# Magileff_transporter.net
KiCad netlist of a schematic drawn in EAGLE
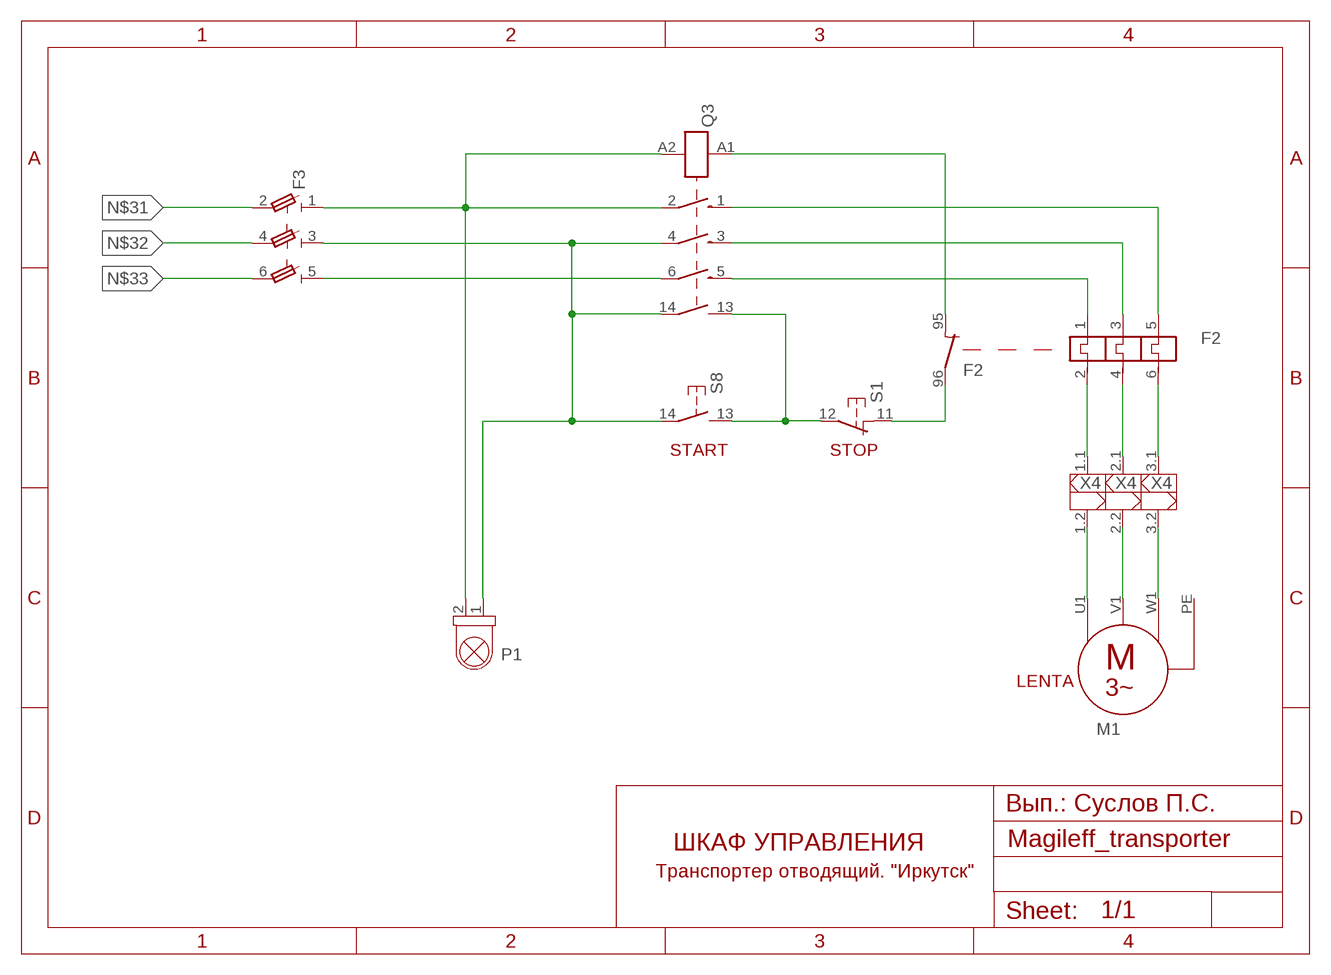
[diagram p0: schematic, sheet 1]

(export (version "E")
  (design (tool "Eeschema 10.0.6"))
  (components
    (comp (ref "F2")
      (value "MOTORSCHUTZSCHALTER_3-POL_THERM_AUSLOESUNG_HILFSKONTAKTE")
      (footprint "eagle-import:MOTORSCHUTZSCHALTER_3-POL_THERM_AUSLOESUNG_HILFSKONTAKT_95_96_97_98")
      (libsource (lib "eagle-import") (part "MOTORSCHUTZSCHALTER_3-POL_THERM_AUSLOESUNG_HILFSKONTAKTE"))
    )
    (comp (ref "F3")
      (value "TRENNSICHERUNG_3-POL")
      (footprint "eagle-import:TRENNSICHERUNG_3-POL")
      (libsource (lib "eagle-import") (part "TRENNSICHERUNG_3-POL"))
    )
    (comp (ref "M1")
      (value "MOTOR_3-POL_PE")
      (footprint "eagle-import:MOTOR_3-POL_PE")
      (libsource (lib "eagle-import") (part "MOTOR_3-POL_PE"))
    )
    (comp (ref "P1")
      (value "BLINK/BLITZLEUCHTE")
      (footprint "eagle-import:LAMPE")
      (libsource (lib "eagle-import") (part "BLINK/BLITZLEUCHTE"))
    )
    (comp (ref "Q3")
      (value "HAUPTSCHUETZ_3-POL_HILFSKONTAKT_13-14_OHNE_KONTAKTSPIEGEL")
      (footprint "eagle-import:HAUPTSCHUETZ_3-POL+HILFSKONTAKT_13-14_OHNE_KONTAKTSPIEGEL")
      (libsource (lib "eagle-import") (part "HAUPTSCHUETZ_3-POL_HILFSKONTAKT_13-14_OHNE_KONTAKTSPIEGEL"))
    )
    (comp (ref "S1")
      (value "OEFFNER_TASTSCHALTER")
      (footprint "eagle-import:OEFFNER_TASTSCHALTER")
      (libsource (lib "eagle-import") (part "OEFFNER_TASTSCHALTER"))
    )
    (comp (ref "S8")
      (value "SCHLIESSER_TASTSCHALTER")
      (footprint "eagle-import:SCHLIESSER_TASTSCHALTER")
      (libsource (lib "eagle-import") (part "SCHLIESSER_TASTSCHALTER"))
    )
    (comp (ref "X4")
      (value "KLEMME-2_3-BRUECKE")
      (footprint "eagle-import:KLEMME-2_3-BRUECKE")
      (libsource (lib "eagle-import") (part "KLEMME-2_3-BRUECKE"))
    )
  )
  (nets
    (net (code "1") (name "N$31") (class "Default")
      (node (ref "F3") (pin "2") (pinfunction "2_2") (pintype "passive"))
    )
    (net (code "2") (name "N$32") (class "Default")
      (node (ref "F3") (pin "4") (pinfunction "4_4") (pintype "passive"))
    )
    (net (code "3") (name "N$33") (class "Default")
      (node (ref "F3") (pin "6") (pinfunction "6_6") (pintype "passive"))
    )
    (net (code "4") (name "Net-(F2-Pad1)") (class "Default")
      (node (ref "F2") (pin "1") (pinfunction "1_1") (pintype "passive"))
      (node (ref "Q3") (pin "5") (pinfunction "5_5") (pintype "passive"))
    )
    (net (code "5") (name "Net-(F2-Pad3)") (class "Default")
      (node (ref "F2") (pin "3") (pinfunction "3_3") (pintype "passive"))
      (node (ref "Q3") (pin "3") (pinfunction "3_3") (pintype "passive"))
    )
    (net (code "6") (name "Net-(F2-Pad5)") (class "Default")
      (node (ref "F2") (pin "5") (pinfunction "5_5") (pintype "passive"))
      (node (ref "Q3") (pin "1") (pinfunction "1_1") (pintype "passive"))
    )
    (net (code "7") (name "Net-(F2-Pad95)") (class "Default")
      (node (ref "F2") (pin "95") (pinfunction "95_95") (pintype "passive"))
      (node (ref "Q3") (pin "A1") (pinfunction "A1_A1") (pintype "input"))
    )
    (net (code "8") (name "Net-(F3-Pad5)") (class "Default")
      (node (ref "F3") (pin "5") (pinfunction "5_5") (pintype "passive"))
      (node (ref "Q3") (pin "6") (pinfunction "6_6") (pintype "passive"))
    )
    (net (code "9") (name "Net-(P1-X1)") (class "Default")
      (node (ref "F3") (pin "3") (pinfunction "3_3") (pintype "passive"))
      (node (ref "P1") (pin "1") (pinfunction "X1_1") (pintype "passive"))
      (node (ref "Q3") (pin "14") (pinfunction "8_14") (pintype "passive"))
      (node (ref "Q3") (pin "4") (pinfunction "4_4") (pintype "passive"))
      (node (ref "S8") (pin "14") (pinfunction "4_14") (pintype "input"))
    )
    (net (code "10") (name "Net-(P1-X2)") (class "Default")
      (node (ref "F3") (pin "1") (pinfunction "1_1") (pintype "passive"))
      (node (ref "P1") (pin "2") (pinfunction "X2_2") (pintype "passive"))
      (node (ref "Q3") (pin "2") (pinfunction "2_2") (pintype "passive"))
      (node (ref "Q3") (pin "A2") (pinfunction "A2_A2") (pintype "input"))
    )
    (net (code "11") (name "Net-(Q3-7)") (class "Default")
      (node (ref "Q3") (pin "13") (pinfunction "7_13") (pintype "passive"))
      (node (ref "S1") (pin "12") (pinfunction "2_12") (pintype "input"))
      (node (ref "S8") (pin "13") (pinfunction "3_13") (pintype "input"))
    )
    (net (code "12") (name "Net-(S1-1)") (class "Default")
      (node (ref "F2") (pin "96") (pinfunction "96_96") (pintype "passive"))
      (node (ref "S1") (pin "11") (pinfunction "1_11") (pintype "input"))
    )
    (net (code "13") (name "Net-(X4A-1)") (class "Default")
      (node (ref "F2") (pin "2") (pinfunction "2_2") (pintype "passive"))
      (node (ref "X4") (pin "1.1") (pinfunction "1_1.1") (pintype "passive"))
    )
    (net (code "14") (name "Net-(X4A-2)") (class "Default")
      (node (ref "M1") (pin "U1") (pinfunction "U1_U1") (pintype "passive"))
      (node (ref "X4") (pin "1.2") (pinfunction "2_1.2") (pintype "passive"))
    )
    (net (code "15") (name "Net-(X4B-1)") (class "Default")
      (node (ref "F2") (pin "4") (pinfunction "4_4") (pintype "passive"))
      (node (ref "X4") (pin "2.1") (pinfunction "1_2.1") (pintype "passive"))
    )
    (net (code "16") (name "Net-(X4B-2)") (class "Default")
      (node (ref "M1") (pin "V1") (pinfunction "V1_V1") (pintype "passive"))
      (node (ref "X4") (pin "2.2") (pinfunction "2_2.2") (pintype "passive"))
    )
    (net (code "17") (name "Net-(X4C-1)") (class "Default")
      (node (ref "F2") (pin "6") (pinfunction "6_6") (pintype "passive"))
      (node (ref "X4") (pin "3.1") (pinfunction "1_3.1") (pintype "passive"))
    )
    (net (code "18") (name "Net-(X4C-2)") (class "Default")
      (node (ref "M1") (pin "W1") (pinfunction "W1_W1") (pintype "passive"))
      (node (ref "X4") (pin "3.2") (pinfunction "2_3.2") (pintype "passive"))
    )
    (net (code "19") (name "unconnected-(M1-PadPE)") (class "Default")
      (node (ref "M1") (pin "PE") (pinfunction "PE_PE") (pintype "passive"))
    )
  )
)
